# 4_-RF.net
KiCad netlist of a schematic drawn in Altium Designer
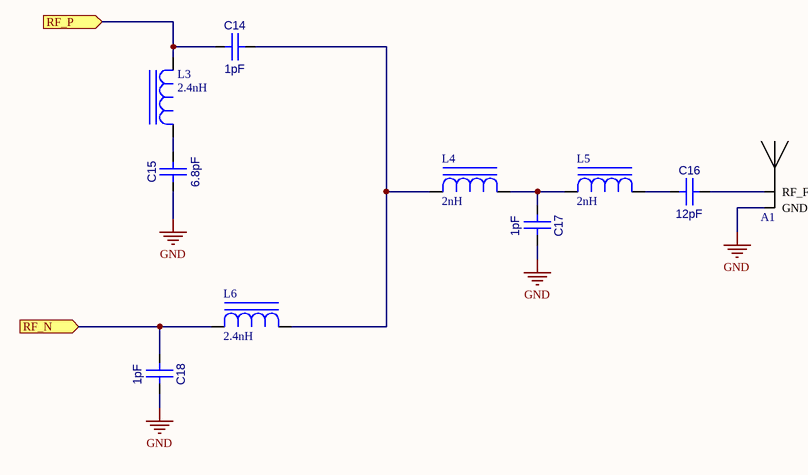
[diagram p0: [4]-RF.SchDoc]

(export (version "E")
  (design (tool "Eeschema 10.0.6"))
  (components
    (comp (ref "A1")
      (value "Antenna Wi-Fi")
      (footprint "Antenna_WiFi")
      (description "2.43GHz")
      (libsource (lib "fizik_lib") (part "Antenna Wi-Fi"))
    )
    (comp (ref "C14")
      (value "1pF")
      (footprint "CC0603")
      (description "CC0603")
      (libsource (lib "gprs_modem_2") (part "CC0603"))
    )
    (comp (ref "C15")
      (value "6.8pF")
      (footprint "CC0603")
      (description "CC0603")
      (libsource (lib "gprs_modem_2") (part "CC0603"))
    )
    (comp (ref "C16")
      (value "12pF")
      (footprint "CC0603")
      (description "CC0603")
      (libsource (lib "gprs_modem_2") (part "CC0603"))
    )
    (comp (ref "C17")
      (value "1pF")
      (footprint "CC0603")
      (description "CC0603")
      (libsource (lib "gprs_modem_2") (part "CC0603"))
    )
    (comp (ref "C18")
      (value "1pF")
      (footprint "CC0603")
      (description "CC0603")
      (libsource (lib "gprs_modem_2") (part "CC0603"))
    )
    (comp (ref "L3")
      (value "2.4nH")
      (footprint "L0402")
      (description "L0402")
      (libsource (lib "gprs_modem_2") (part "L0402"))
    )
    (comp (ref "L4")
      (value "2nH")
      (footprint "L0402")
      (description "L0402")
      (libsource (lib "gprs_modem_2") (part "L0402"))
    )
    (comp (ref "L5")
      (value "2nH")
      (footprint "L0402")
      (description "L0402")
      (libsource (lib "gprs_modem_2") (part "L0402"))
    )
    (comp (ref "L6")
      (value "2.4nH")
      (footprint "L0402")
      (description "L0402")
      (libsource (lib "gprs_modem_2") (part "L0402"))
    )
  )
  (nets
    (net (code "1") (name "/RF_N") (class "Default")
      (node (ref "C18") (pin "1") (pinfunction "A_1") (pintype "passive"))
      (node (ref "L6") (pin "1") (pinfunction "A_1") (pintype "passive"))
    )
    (net (code "2") (name "/RF_P") (class "Default")
      (node (ref "C14") (pin "1") (pinfunction "A_1") (pintype "passive"))
      (node (ref "L3") (pin "2") (pinfunction "C_2") (pintype "passive"))
    )
    (net (code "3") (name "GND") (class "Default")
      (node (ref "A1") (pin "2") (pinfunction "GND_2") (pintype "passive"))
      (node (ref "C15") (pin "1") (pinfunction "A_1") (pintype "passive"))
      (node (ref "C17") (pin "2") (pinfunction "B_2") (pintype "passive"))
      (node (ref "C18") (pin "2") (pinfunction "B_2") (pintype "passive"))
    )
    (net (code "4") (name "Net-(A1-RF_Feed)") (class "Default")
      (node (ref "A1") (pin "1") (pinfunction "RF_Feed_1") (pintype "passive"))
      (node (ref "C16") (pin "2") (pinfunction "B_2") (pintype "passive"))
    )
    (net (code "5") (name "Net-(C14-B)") (class "Default")
      (node (ref "C14") (pin "2") (pinfunction "B_2") (pintype "passive"))
      (node (ref "L4") (pin "1") (pinfunction "A_1") (pintype "passive"))
      (node (ref "L6") (pin "2") (pinfunction "C_2") (pintype "passive"))
    )
    (net (code "6") (name "Net-(C15-B)") (class "Default")
      (node (ref "C15") (pin "2") (pinfunction "B_2") (pintype "passive"))
      (node (ref "L3") (pin "1") (pinfunction "A_1") (pintype "passive"))
    )
    (net (code "7") (name "Net-(C16-A)") (class "Default")
      (node (ref "C16") (pin "1") (pinfunction "A_1") (pintype "passive"))
      (node (ref "L5") (pin "2") (pinfunction "C_2") (pintype "passive"))
    )
    (net (code "8") (name "Net-(C17-A)") (class "Default")
      (node (ref "C17") (pin "1") (pinfunction "A_1") (pintype "passive"))
      (node (ref "L4") (pin "2") (pinfunction "C_2") (pintype "passive"))
      (node (ref "L5") (pin "1") (pinfunction "A_1") (pintype "passive"))
    )
  )
)
